# fpc-30-lcd-adapter.net
KiCad netlist of a schematic drawn in EAGLE
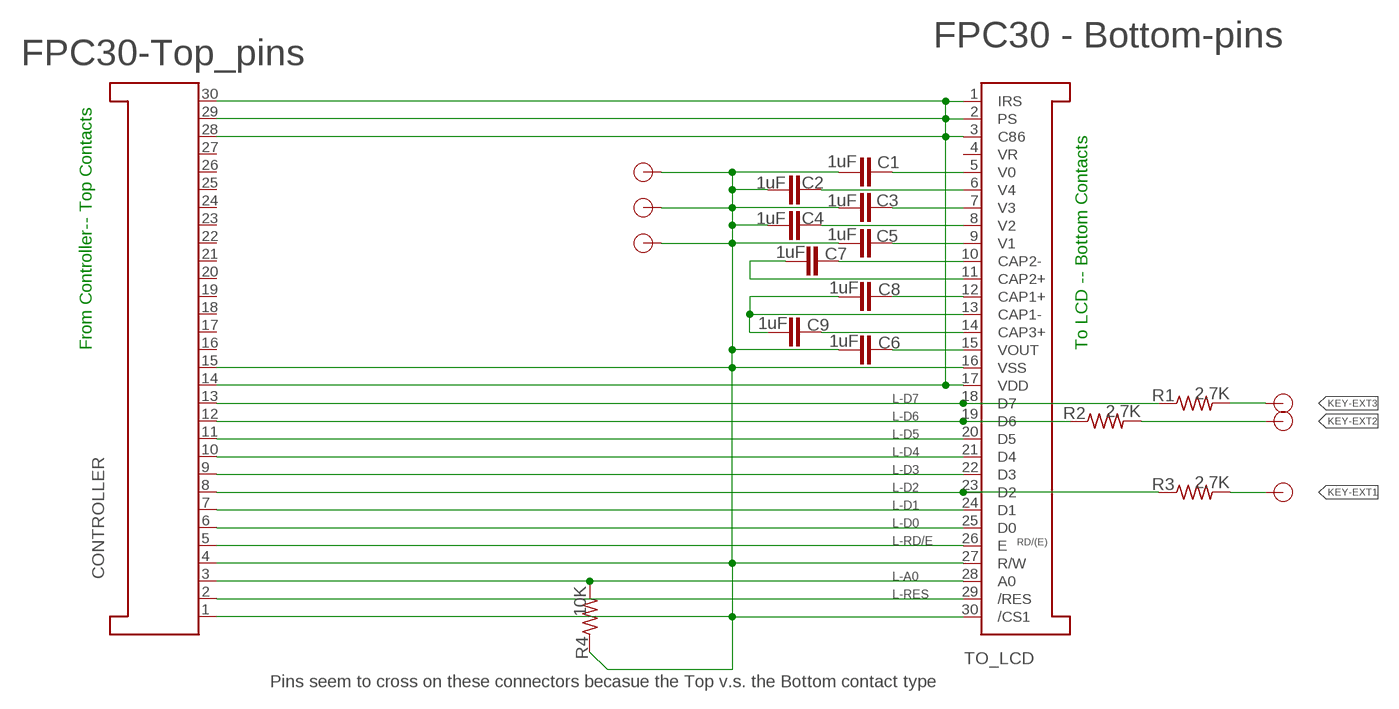
[diagram p0: schematic, sheet 1]

(export (version "E")
  (design (tool "Eeschema 10.0.6"))
  (components
    (comp (ref "C1")
      (value "1uF")
      (footprint "eagle-import:C0805")
      (libsource (lib "eagle-import") (part "C-EUC0805"))
    )
    (comp (ref "C2")
      (value "1uF")
      (footprint "eagle-import:C0805")
      (libsource (lib "eagle-import") (part "C-EUC0805"))
    )
    (comp (ref "C3")
      (value "1uF")
      (footprint "eagle-import:C0805")
      (libsource (lib "eagle-import") (part "C-EUC0805"))
    )
    (comp (ref "C4")
      (value "1uF")
      (footprint "eagle-import:C0805")
      (libsource (lib "eagle-import") (part "C-EUC0805"))
    )
    (comp (ref "C5")
      (value "1uF")
      (footprint "eagle-import:C0805")
      (libsource (lib "eagle-import") (part "C-EUC0805"))
    )
    (comp (ref "C6")
      (value "1uF")
      (footprint "eagle-import:C0805")
      (libsource (lib "eagle-import") (part "C-EUC0805"))
    )
    (comp (ref "C7")
      (value "1uF")
      (footprint "eagle-import:C0805")
      (libsource (lib "eagle-import") (part "C-EUC0805"))
    )
    (comp (ref "C8")
      (value "1uF")
      (footprint "eagle-import:C0805")
      (libsource (lib "eagle-import") (part "C-EUC0805"))
    )
    (comp (ref "C9")
      (value "1uF")
      (footprint "eagle-import:C0805")
      (libsource (lib "eagle-import") (part "C-EUC0805"))
    )
    (comp (ref "CONTROLLER")
      (value "FPC30-Top_pins")
      (footprint "eagle-import:FH12-30S-0.5SH")
      (libsource (lib "eagle-import") (part "FPC_30-PINS"))
    )
    (comp (ref "EXT1")
      (value "TP-1")
      (footprint "eagle-import:TP")
      (libsource (lib "eagle-import") (part "TP-1"))
    )
    (comp (ref "EXT2")
      (value "TP-1")
      (footprint "eagle-import:TP")
      (libsource (lib "eagle-import") (part "TP-1"))
    )
    (comp (ref "EXT3")
      (value "TP-1")
      (footprint "eagle-import:TP")
      (libsource (lib "eagle-import") (part "TP-1"))
    )
    (comp (ref "K_EXT4")
      (value "TP-1")
      (footprint "eagle-import:TP")
      (libsource (lib "eagle-import") (part "TP-1"))
    )
    (comp (ref "K_EXT5")
      (value "TP-1")
      (footprint "eagle-import:TP")
      (libsource (lib "eagle-import") (part "TP-1"))
    )
    (comp (ref "K_EXT6")
      (value "TP-1")
      (footprint "eagle-import:TP")
      (libsource (lib "eagle-import") (part "TP-1"))
    )
    (comp (ref "R1")
      (value "2.7K")
      (footprint "eagle-import:R0603")
      (libsource (lib "eagle-import") (part "R-US_R0603"))
    )
    (comp (ref "R2")
      (value "2.7K")
      (footprint "eagle-import:R0603")
      (libsource (lib "eagle-import") (part "R-US_R0603"))
    )
    (comp (ref "R3")
      (value "2.7K")
      (footprint "eagle-import:R0603")
      (libsource (lib "eagle-import") (part "R-US_R0603"))
    )
    (comp (ref "R4")
      (value "10K")
      (footprint "eagle-import:R0603")
      (libsource (lib "eagle-import") (part "R-US_R0603"))
    )
    (comp (ref "TO_LCD")
      (value "FPC30 - Bottom-pins")
      (footprint "eagle-import:FH12-30S-0.5SH")
      (libsource (lib "eagle-import") (part "FPC_30_ERC12864-2"))
    )
  )
  (nets
    (net (code "1") (name "/L-A0") (class "Default")
      (node (ref "CONTROLLER") (pin "3") (pinfunction "P$3_3") (pintype "bidirectional"))
      (node (ref "R4") (pin "2") (pinfunction "2_2") (pintype "passive"))
      (node (ref "TO_LCD") (pin "28") (pinfunction "A0_28") (pintype "bidirectional"))
    )
    (net (code "2") (name "/L-D0") (class "Default")
      (node (ref "CONTROLLER") (pin "6") (pinfunction "P$6_6") (pintype "bidirectional"))
      (node (ref "TO_LCD") (pin "25") (pinfunction "D0_25") (pintype "bidirectional"))
    )
    (net (code "3") (name "/L-D1") (class "Default")
      (node (ref "CONTROLLER") (pin "7") (pinfunction "P$7_7") (pintype "bidirectional"))
      (node (ref "TO_LCD") (pin "24") (pinfunction "D1_24") (pintype "bidirectional"))
    )
    (net (code "4") (name "/L-D2") (class "Default")
      (node (ref "CONTROLLER") (pin "8") (pinfunction "P$8_8") (pintype "bidirectional"))
      (node (ref "R3") (pin "1") (pinfunction "1_1") (pintype "passive"))
      (node (ref "TO_LCD") (pin "23") (pinfunction "D2_23") (pintype "bidirectional"))
    )
    (net (code "5") (name "/L-D3") (class "Default")
      (node (ref "CONTROLLER") (pin "9") (pinfunction "P$9_9") (pintype "bidirectional"))
      (node (ref "TO_LCD") (pin "22") (pinfunction "D3_22") (pintype "bidirectional"))
    )
    (net (code "6") (name "/L-D4") (class "Default")
      (node (ref "CONTROLLER") (pin "10") (pinfunction "P$10_10") (pintype "bidirectional"))
      (node (ref "TO_LCD") (pin "21") (pinfunction "D4_21") (pintype "bidirectional"))
    )
    (net (code "7") (name "/L-D5") (class "Default")
      (node (ref "CONTROLLER") (pin "11") (pinfunction "P$11_11") (pintype "bidirectional"))
      (node (ref "TO_LCD") (pin "20") (pinfunction "D5_20") (pintype "bidirectional"))
    )
    (net (code "8") (name "/L-D6") (class "Default")
      (node (ref "CONTROLLER") (pin "12") (pinfunction "P$12_12") (pintype "bidirectional"))
      (node (ref "R2") (pin "1") (pinfunction "1_1") (pintype "passive"))
      (node (ref "TO_LCD") (pin "19") (pinfunction "D6_19") (pintype "bidirectional"))
    )
    (net (code "9") (name "/L-D7") (class "Default")
      (node (ref "CONTROLLER") (pin "13") (pinfunction "P$13_13") (pintype "bidirectional"))
      (node (ref "R1") (pin "1") (pinfunction "1_1") (pintype "passive"))
      (node (ref "TO_LCD") (pin "18") (pinfunction "D7_18") (pintype "bidirectional"))
    )
    (net (code "10") (name "/L-RD{slash}E") (class "Default")
      (node (ref "CONTROLLER") (pin "5") (pinfunction "P$5_5") (pintype "bidirectional"))
      (node (ref "TO_LCD") (pin "26") (pinfunction "E_26") (pintype "bidirectional"))
    )
    (net (code "11") (name "/L-RES") (class "Default")
      (node (ref "CONTROLLER") (pin "2") (pinfunction "P$2_2") (pintype "bidirectional"))
      (node (ref "TO_LCD") (pin "29") (pinfunction "/RES_29") (pintype "bidirectional"))
    )
    (net (code "12") (name "KEY-EXT1") (class "Default")
      (node (ref "EXT1") (pin "P$1") (pinfunction "P$1_P$1") (pintype "bidirectional"))
      (node (ref "R3") (pin "2") (pinfunction "2_2") (pintype "passive"))
    )
    (net (code "13") (name "KEY-EXT2") (class "Default")
      (node (ref "EXT2") (pin "P$1") (pinfunction "P$1_P$1") (pintype "bidirectional"))
      (node (ref "R2") (pin "2") (pinfunction "2_2") (pintype "passive"))
    )
    (net (code "14") (name "KEY-EXT3") (class "Default")
      (node (ref "EXT3") (pin "P$1") (pinfunction "P$1_P$1") (pintype "bidirectional"))
      (node (ref "R1") (pin "2") (pinfunction "2_2") (pintype "passive"))
    )
    (net (code "15") (name "Net-(CONTROLLER-P$1)") (class "Default")
      (node (ref "C1") (pin "2") (pinfunction "2_2") (pintype "passive"))
      (node (ref "C2") (pin "2") (pinfunction "2_2") (pintype "passive"))
      (node (ref "C3") (pin "2") (pinfunction "2_2") (pintype "passive"))
      (node (ref "C4") (pin "2") (pinfunction "2_2") (pintype "passive"))
      (node (ref "C5") (pin "2") (pinfunction "2_2") (pintype "passive"))
      (node (ref "C6") (pin "2") (pinfunction "2_2") (pintype "passive"))
      (node (ref "CONTROLLER") (pin "1") (pinfunction "P$1_1") (pintype "bidirectional"))
      (node (ref "CONTROLLER") (pin "15") (pinfunction "P$15_15") (pintype "bidirectional"))
      (node (ref "CONTROLLER") (pin "4") (pinfunction "P$4_4") (pintype "bidirectional"))
      (node (ref "K_EXT4") (pin "P$1") (pinfunction "P$1_P$1") (pintype "bidirectional"))
      (node (ref "K_EXT5") (pin "P$1") (pinfunction "P$1_P$1") (pintype "bidirectional"))
      (node (ref "K_EXT6") (pin "P$1") (pinfunction "P$1_P$1") (pintype "bidirectional"))
      (node (ref "R4") (pin "1") (pinfunction "1_1") (pintype "passive"))
      (node (ref "TO_LCD") (pin "16") (pinfunction "VSS_16") (pintype "bidirectional"))
      (node (ref "TO_LCD") (pin "27") (pinfunction "R/W_27") (pintype "bidirectional"))
      (node (ref "TO_LCD") (pin "30") (pinfunction "/CS1_30") (pintype "bidirectional"))
    )
    (net (code "16") (name "Net-(CONTROLLER-P$14)") (class "Default")
      (node (ref "CONTROLLER") (pin "14") (pinfunction "P$14_14") (pintype "bidirectional"))
      (node (ref "CONTROLLER") (pin "28") (pinfunction "P$28_28") (pintype "bidirectional"))
      (node (ref "CONTROLLER") (pin "29") (pinfunction "P$29_29") (pintype "bidirectional"))
      (node (ref "CONTROLLER") (pin "30") (pinfunction "P$30_30") (pintype "bidirectional"))
      (node (ref "TO_LCD") (pin "1") (pinfunction "IRS_1") (pintype "bidirectional"))
      (node (ref "TO_LCD") (pin "17") (pinfunction "VDD_17") (pintype "bidirectional"))
      (node (ref "TO_LCD") (pin "2") (pinfunction "PS_2") (pintype "bidirectional"))
      (node (ref "TO_LCD") (pin "3") (pinfunction "C86_3") (pintype "bidirectional"))
    )
    (net (code "17") (name "Net-(TO_LCD-CAP1+)") (class "Default")
      (node (ref "C8") (pin "1") (pinfunction "1_1") (pintype "passive"))
      (node (ref "TO_LCD") (pin "12") (pinfunction "CAP1+_12") (pintype "bidirectional"))
    )
    (net (code "18") (name "Net-(TO_LCD-CAP1-)") (class "Default")
      (node (ref "C8") (pin "2") (pinfunction "2_2") (pintype "passive"))
      (node (ref "C9") (pin "2") (pinfunction "2_2") (pintype "passive"))
      (node (ref "TO_LCD") (pin "13") (pinfunction "CAP1-_13") (pintype "bidirectional"))
    )
    (net (code "19") (name "Net-(TO_LCD-CAP2+)") (class "Default")
      (node (ref "C7") (pin "2") (pinfunction "2_2") (pintype "passive"))
      (node (ref "TO_LCD") (pin "11") (pinfunction "CAP2+_11") (pintype "bidirectional"))
    )
    (net (code "20") (name "Net-(TO_LCD-CAP2-)") (class "Default")
      (node (ref "C7") (pin "1") (pinfunction "1_1") (pintype "passive"))
      (node (ref "TO_LCD") (pin "10") (pinfunction "CAP2-_10") (pintype "bidirectional"))
    )
    (net (code "21") (name "Net-(TO_LCD-CAP3+)") (class "Default")
      (node (ref "C9") (pin "1") (pinfunction "1_1") (pintype "passive"))
      (node (ref "TO_LCD") (pin "14") (pinfunction "CAP3+_14") (pintype "bidirectional"))
    )
    (net (code "22") (name "Net-(TO_LCD-V0)") (class "Default")
      (node (ref "C1") (pin "1") (pinfunction "1_1") (pintype "passive"))
      (node (ref "TO_LCD") (pin "5") (pinfunction "V0_5") (pintype "bidirectional"))
    )
    (net (code "23") (name "Net-(TO_LCD-V1)") (class "Default")
      (node (ref "C5") (pin "1") (pinfunction "1_1") (pintype "passive"))
      (node (ref "TO_LCD") (pin "9") (pinfunction "V1_9") (pintype "bidirectional"))
    )
    (net (code "24") (name "Net-(TO_LCD-V2)") (class "Default")
      (node (ref "C4") (pin "1") (pinfunction "1_1") (pintype "passive"))
      (node (ref "TO_LCD") (pin "8") (pinfunction "V2_8") (pintype "bidirectional"))
    )
    (net (code "25") (name "Net-(TO_LCD-V3)") (class "Default")
      (node (ref "C3") (pin "1") (pinfunction "1_1") (pintype "passive"))
      (node (ref "TO_LCD") (pin "7") (pinfunction "V3_7") (pintype "bidirectional"))
    )
    (net (code "26") (name "Net-(TO_LCD-V4)") (class "Default")
      (node (ref "C2") (pin "1") (pinfunction "1_1") (pintype "passive"))
      (node (ref "TO_LCD") (pin "6") (pinfunction "V4_6") (pintype "bidirectional"))
    )
    (net (code "27") (name "Net-(TO_LCD-VOUT)") (class "Default")
      (node (ref "C6") (pin "1") (pinfunction "1_1") (pintype "passive"))
      (node (ref "TO_LCD") (pin "15") (pinfunction "VOUT_15") (pintype "bidirectional"))
    )
    (net (code "28") (name "unconnected-(CONTROLLER-P$16-Pad16)") (class "Default")
      (node (ref "CONTROLLER") (pin "16") (pinfunction "P$16_16") (pintype "bidirectional"))
    )
    (net (code "29") (name "unconnected-(CONTROLLER-P$17-Pad17)") (class "Default")
      (node (ref "CONTROLLER") (pin "17") (pinfunction "P$17_17") (pintype "bidirectional"))
    )
    (net (code "30") (name "unconnected-(CONTROLLER-P$18-Pad18)") (class "Default")
      (node (ref "CONTROLLER") (pin "18") (pinfunction "P$18_18") (pintype "bidirectional"))
    )
    (net (code "31") (name "unconnected-(CONTROLLER-P$19-Pad19)") (class "Default")
      (node (ref "CONTROLLER") (pin "19") (pinfunction "P$19_19") (pintype "bidirectional"))
    )
    (net (code "32") (name "unconnected-(CONTROLLER-P$20-Pad20)") (class "Default")
      (node (ref "CONTROLLER") (pin "20") (pinfunction "P$20_20") (pintype "bidirectional"))
    )
    (net (code "33") (name "unconnected-(CONTROLLER-P$21-Pad21)") (class "Default")
      (node (ref "CONTROLLER") (pin "21") (pinfunction "P$21_21") (pintype "bidirectional"))
    )
    (net (code "34") (name "unconnected-(CONTROLLER-P$22-Pad22)") (class "Default")
      (node (ref "CONTROLLER") (pin "22") (pinfunction "P$22_22") (pintype "bidirectional"))
    )
    (net (code "35") (name "unconnected-(CONTROLLER-P$23-Pad23)") (class "Default")
      (node (ref "CONTROLLER") (pin "23") (pinfunction "P$23_23") (pintype "bidirectional"))
    )
    (net (code "36") (name "unconnected-(CONTROLLER-P$24-Pad24)") (class "Default")
      (node (ref "CONTROLLER") (pin "24") (pinfunction "P$24_24") (pintype "bidirectional"))
    )
    (net (code "37") (name "unconnected-(CONTROLLER-P$25-Pad25)") (class "Default")
      (node (ref "CONTROLLER") (pin "25") (pinfunction "P$25_25") (pintype "bidirectional"))
    )
    (net (code "38") (name "unconnected-(CONTROLLER-P$26-Pad26)") (class "Default")
      (node (ref "CONTROLLER") (pin "26") (pinfunction "P$26_26") (pintype "bidirectional"))
    )
    (net (code "39") (name "unconnected-(CONTROLLER-P$27-Pad27)") (class "Default")
      (node (ref "CONTROLLER") (pin "27") (pinfunction "P$27_27") (pintype "bidirectional"))
    )
    (net (code "40") (name "unconnected-(TO_LCD-VR-Pad4)") (class "Default")
      (node (ref "TO_LCD") (pin "4") (pinfunction "VR_4") (pintype "bidirectional"))
    )
  )
)
